# Feuermelder.net
KiCad netlist of a schematic drawn in EAGLE
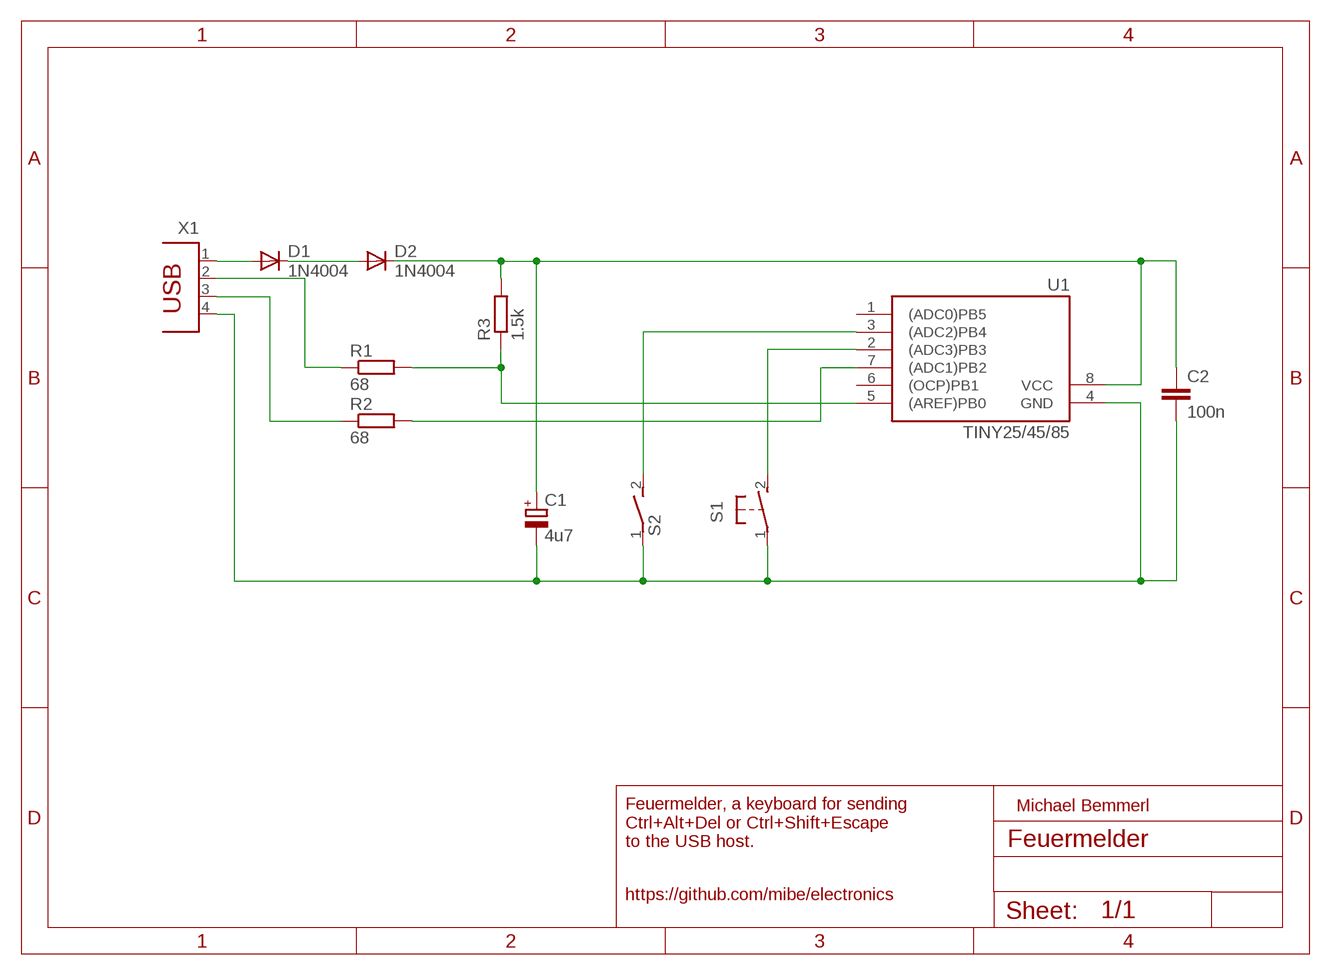
[diagram p0: schematic, sheet 1]

(export (version "E")
  (design (tool "Eeschema 10.0.6"))
  (components
    (comp (ref "C1")
      (value "4u7")
      (footprint "eagle-import:E2,5-6")
      (libsource (lib "eagle-import") (part "CPOL-EUE2.5-6"))
    )
    (comp (ref "C2")
      (value "100n")
      (footprint "eagle-import:C050-025X075")
      (libsource (lib "eagle-import") (part "C-EU050-025X075"))
    )
    (comp (ref "D1")
      (value "1N4004")
      (footprint "eagle-import:DO41-10")
      (libsource (lib "eagle-import") (part "1N4004"))
    )
    (comp (ref "D2")
      (value "1N4004")
      (footprint "eagle-import:DO41-10")
      (libsource (lib "eagle-import") (part "1N4004"))
    )
    (comp (ref "R1")
      (value "68")
      (footprint "eagle-import:0207_10")
      (libsource (lib "eagle-import") (part "R-EU_0207/10"))
    )
    (comp (ref "R2")
      (value "68")
      (footprint "eagle-import:0207_10")
      (libsource (lib "eagle-import") (part "R-EU_0207/10"))
    )
    (comp (ref "R3")
      (value "1.5k")
      (footprint "eagle-import:0207_10")
      (libsource (lib "eagle-import") (part "R-EU_0207/10"))
    )
    (comp (ref "S1")
      (value "31-XX")
      (footprint "eagle-import:B3F-31XX")
      (fields (field (name "MPN") "B3F-3100"))
      (libsource (lib "eagle-import") (part "31-XX"))
    )
    (comp (ref "S2")
      (value "DS01E")
      (footprint "eagle-import:DS-01")
      (libsource (lib "eagle-import") (part "DS01E"))
    )
    (comp (ref "U1")
      (value "TINY25/45/85")
      (footprint "eagle-import:DIL08")
      (libsource (lib "eagle-import") (part "TINY25/45/85"))
    )
    (comp (ref "X1")
      (value "PN61729")
      (footprint "eagle-import:PN61729")
      (libsource (lib "eagle-import") (part "PN61729"))
    )
  )
  (nets
    (net (code "1") (name "Net-(D1-PadA)") (class "Default")
      (node (ref "D1") (pin "A") (pinfunction "A_A") (pintype "passive"))
      (node (ref "X1") (pin "1") (pinfunction "1_1") (pintype "passive"))
    )
    (net (code "2") (name "Net-(D1-PadC)") (class "Default")
      (node (ref "D1") (pin "C") (pinfunction "C_C") (pintype "passive"))
      (node (ref "D2") (pin "A") (pinfunction "A_A") (pintype "passive"))
    )
    (net (code "3") (name "Net-(R1-Pad1)") (class "Default")
      (node (ref "R1") (pin "1") (pinfunction "1_1") (pintype "passive"))
      (node (ref "X1") (pin "2") (pinfunction "2_2") (pintype "passive"))
    )
    (net (code "4") (name "Net-(R2-Pad1)") (class "Default")
      (node (ref "R2") (pin "1") (pinfunction "1_1") (pintype "passive"))
      (node (ref "X1") (pin "3") (pinfunction "3_3") (pintype "passive"))
    )
    (net (code "5") (name "Net-(S1-P)") (class "Default")
      (node (ref "C1") (pin "-") (pinfunction "-_-") (pintype "passive"))
      (node (ref "C2") (pin "2") (pinfunction "2_2") (pintype "passive"))
      (node (ref "S1") (pin "1") (pinfunction "P_1") (pintype "passive"))
      (node (ref "S2") (pin "1") (pinfunction "1_1") (pintype "passive"))
      (node (ref "U1") (pin "4") (pinfunction "GND_4") (pintype "power_in"))
      (node (ref "X1") (pin "4") (pinfunction "4_4") (pintype "passive"))
    )
    (net (code "6") (name "Net-(S1-S)") (class "Default")
      (node (ref "S1") (pin "2") (pinfunction "S_2") (pintype "passive"))
      (node (ref "U1") (pin "2") (pinfunction "(ADC3)PB3_2") (pintype "bidirectional"))
    )
    (net (code "7") (name "Net-(U1-(ADC1)PB2)") (class "Default")
      (node (ref "R2") (pin "2") (pinfunction "2_2") (pintype "passive"))
      (node (ref "U1") (pin "7") (pinfunction "(ADC1)PB2_7") (pintype "bidirectional"))
    )
    (net (code "8") (name "Net-(U1-(ADC2)PB4)") (class "Default")
      (node (ref "S2") (pin "2") (pinfunction "2_2") (pintype "passive"))
      (node (ref "U1") (pin "3") (pinfunction "(ADC2)PB4_3") (pintype "bidirectional"))
    )
    (net (code "9") (name "Net-(U1-(AREF)PB0)") (class "Default")
      (node (ref "R1") (pin "2") (pinfunction "2_2") (pintype "passive"))
      (node (ref "R3") (pin "1") (pinfunction "1_1") (pintype "passive"))
      (node (ref "U1") (pin "5") (pinfunction "(AREF)PB0_5") (pintype "bidirectional"))
    )
    (net (code "10") (name "Net-(U1-VCC)") (class "Default")
      (node (ref "C1") (pin "+") (pinfunction "+_+") (pintype "passive"))
      (node (ref "C2") (pin "1") (pinfunction "1_1") (pintype "passive"))
      (node (ref "D2") (pin "C") (pinfunction "C_C") (pintype "passive"))
      (node (ref "R3") (pin "2") (pinfunction "2_2") (pintype "passive"))
      (node (ref "U1") (pin "8") (pinfunction "VCC_8") (pintype "power_in"))
    )
    (net (code "11") (name "unconnected-(U1-(ADC0)PB5-Pad1)") (class "Default")
      (node (ref "U1") (pin "1") (pinfunction "(ADC0)PB5_1") (pintype "bidirectional"))
    )
    (net (code "12") (name "unconnected-(U1-(OCP)PB1-Pad6)") (class "Default")
      (node (ref "U1") (pin "6") (pinfunction "(OCP)PB1_6") (pintype "bidirectional"))
    )
  )
)
